# i2c1.net
KiCad netlist of a schematic drawn in Altium Designer
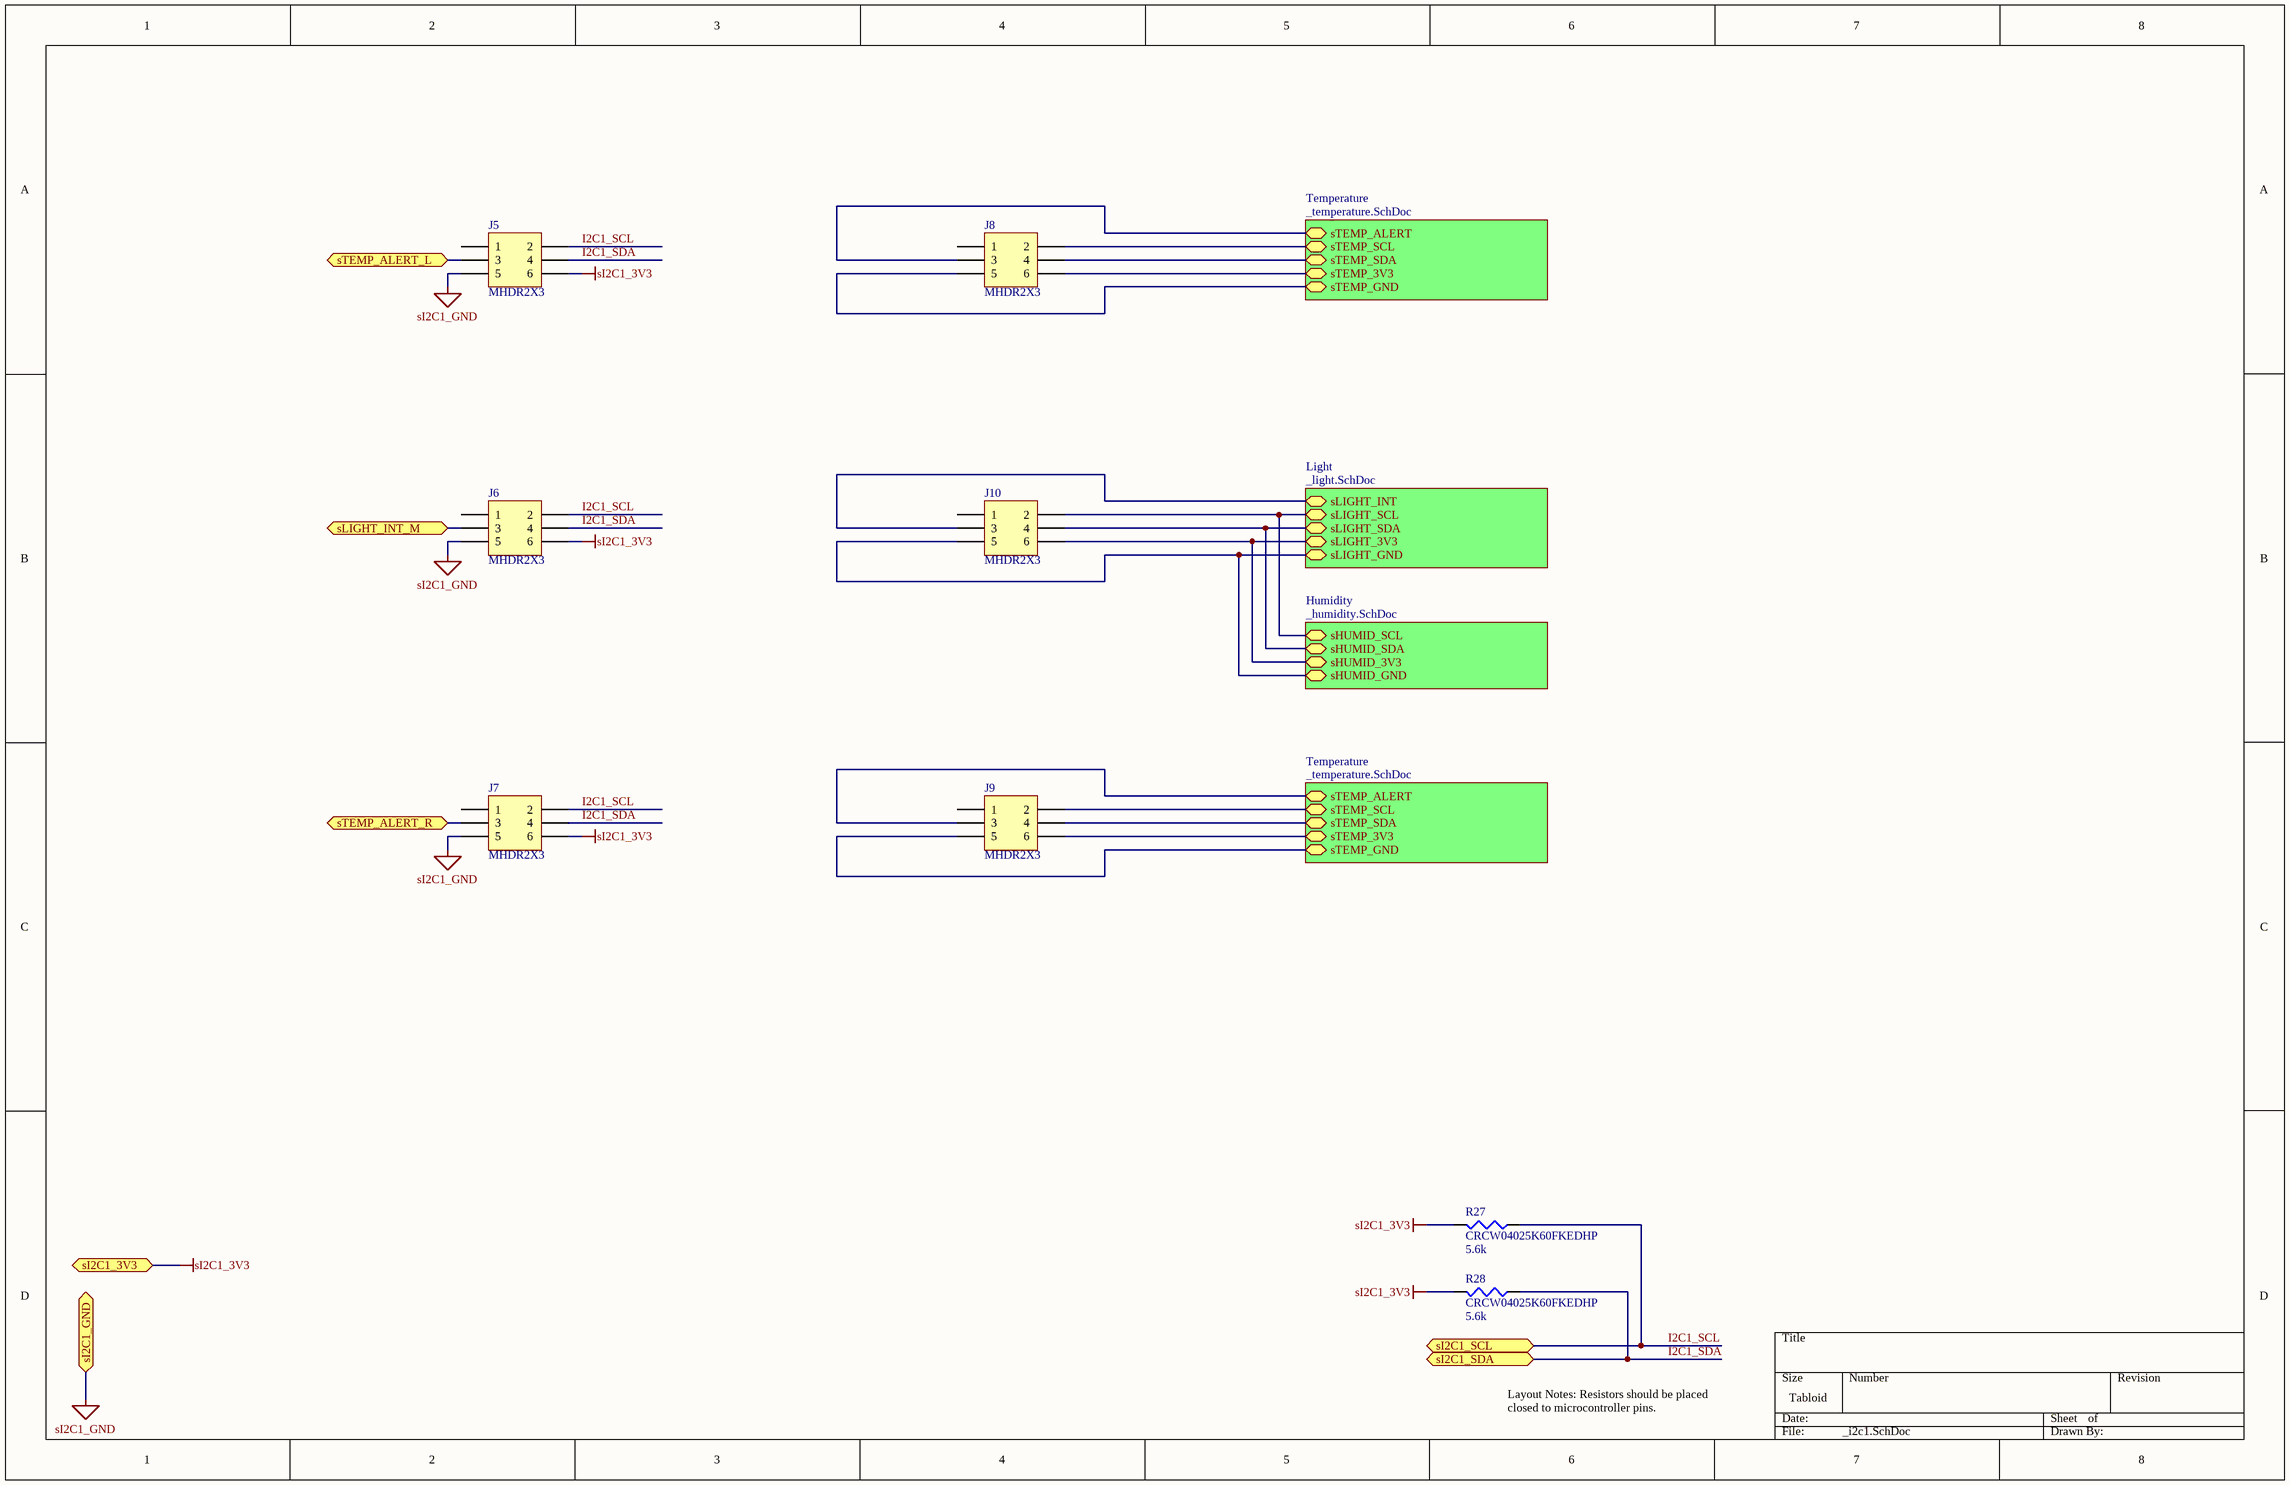
[diagram p0: _i2c1.SchDoc]

(export (version "E")
  (design (tool "Eeschema 10.0.6"))
  (components
    (comp (ref "J5")
      (value "MHDR2X3")
      (footprint "MHDR2X3")
      (description "Header, 3-Pin, Dual row")
      (fields (field (name "PUBLISHER") "Altium Limited"))
      (libsource (lib "Miscellaneous Connectors") (part "MHDR2X3"))
    )
    (comp (ref "J6")
      (value "MHDR2X3")
      (footprint "MHDR2X3")
      (description "Header, 3-Pin, Dual row")
      (fields (field (name "PUBLISHER") "Altium Limited"))
      (libsource (lib "Miscellaneous Connectors") (part "MHDR2X3"))
    )
    (comp (ref "J7")
      (value "MHDR2X3")
      (footprint "MHDR2X3")
      (description "Header, 3-Pin, Dual row")
      (fields (field (name "PUBLISHER") "Altium Limited"))
      (libsource (lib "Miscellaneous Connectors") (part "MHDR2X3"))
    )
    (comp (ref "J8")
      (value "MHDR2X3")
      (footprint "MHDR2X3")
      (description "Header, 3-Pin, Dual row")
      (fields (field (name "PUBLISHER") "Altium Limited"))
      (libsource (lib "Miscellaneous Connectors") (part "MHDR2X3"))
    )
    (comp (ref "J9")
      (value "MHDR2X3")
      (footprint "MHDR2X3")
      (description "Header, 3-Pin, Dual row")
      (fields (field (name "PUBLISHER") "Altium Limited"))
      (libsource (lib "Miscellaneous Connectors") (part "MHDR2X3"))
    )
    (comp (ref "J10")
      (value "MHDR2X3")
      (footprint "MHDR2X3")
      (description "Header, 3-Pin, Dual row")
      (fields (field (name "PUBLISHER") "Altium Limited"))
      (libsource (lib "Miscellaneous Connectors") (part "MHDR2X3"))
    )
    (comp (ref "R27")
      (value "CRCW04025K60FKEDHP")
      (footprint "0402")
      (description "0.125W, -55-155C, 1005, 50V, ±1%")
      (fields (field (name "ALTIUM_VALUE") "5.6k"))
      (libsource (lib "standard_resistors") (part "CRCW0402xxxxFKED"))
    )
    (comp (ref "R28")
      (value "CRCW04025K60FKEDHP")
      (footprint "0402")
      (description "0.125W, -55-155C, 1005, 50V, ±1%")
      (fields (field (name "ALTIUM_VALUE") "5.6k"))
      (libsource (lib "standard_resistors") (part "CRCW0402xxxxFKED"))
    )
  )
  (nets
    (net (code "1") (name "/I2C1_SCL") (class "Default")
      (node (ref "J5") (pin "2") (pinfunction "2_2") (pintype "passive"))
      (node (ref "J6") (pin "2") (pinfunction "2_2") (pintype "passive"))
      (node (ref "J7") (pin "2") (pinfunction "2_2") (pintype "passive"))
      (node (ref "R27") (pin "1") (pinfunction "1_1") (pintype "passive"))
    )
    (net (code "2") (name "/I2C1_SDA") (class "Default")
      (node (ref "J5") (pin "4") (pinfunction "4_4") (pintype "passive"))
      (node (ref "J6") (pin "4") (pinfunction "4_4") (pintype "passive"))
      (node (ref "J7") (pin "4") (pinfunction "4_4") (pintype "passive"))
      (node (ref "R28") (pin "1") (pinfunction "1_1") (pintype "passive"))
    )
    (net (code "3") (name "/sHUMID_3V3") (class "Default")
      (node (ref "J10") (pin "6") (pinfunction "6_6") (pintype "passive"))
    )
    (net (code "4") (name "/sHUMID_GND") (class "Default")
      (node (ref "J10") (pin "5") (pinfunction "5_5") (pintype "passive"))
    )
    (net (code "5") (name "/sHUMID_SCL") (class "Default")
      (node (ref "J10") (pin "2") (pinfunction "2_2") (pintype "passive"))
    )
    (net (code "6") (name "/sHUMID_SDA") (class "Default")
      (node (ref "J10") (pin "4") (pinfunction "4_4") (pintype "passive"))
    )
    (net (code "7") (name "/sLIGHT_INT") (class "Default")
      (node (ref "J10") (pin "3") (pinfunction "3_3") (pintype "passive"))
    )
    (net (code "8") (name "/sLIGHT_INT_M") (class "Default")
      (node (ref "J6") (pin "3") (pinfunction "3_3") (pintype "passive"))
    )
    (net (code "9") (name "/sTEMP_3V3") (class "Default")
      (node (ref "J8") (pin "6") (pinfunction "6_6") (pintype "passive"))
    )
    (net (code "10") (name "/sTEMP_3V3_1") (class "Default")
      (node (ref "J9") (pin "6") (pinfunction "6_6") (pintype "passive"))
    )
    (net (code "11") (name "/sTEMP_ALERT") (class "Default")
      (node (ref "J8") (pin "3") (pinfunction "3_3") (pintype "passive"))
    )
    (net (code "12") (name "/sTEMP_ALERT_1") (class "Default")
      (node (ref "J9") (pin "3") (pinfunction "3_3") (pintype "passive"))
    )
    (net (code "13") (name "/sTEMP_ALERT_L") (class "Default")
      (node (ref "J5") (pin "3") (pinfunction "3_3") (pintype "passive"))
    )
    (net (code "14") (name "/sTEMP_ALERT_R") (class "Default")
      (node (ref "J7") (pin "3") (pinfunction "3_3") (pintype "passive"))
    )
    (net (code "15") (name "/sTEMP_GND") (class "Default")
      (node (ref "J8") (pin "5") (pinfunction "5_5") (pintype "passive"))
    )
    (net (code "16") (name "/sTEMP_GND_1") (class "Default")
      (node (ref "J9") (pin "5") (pinfunction "5_5") (pintype "passive"))
    )
    (net (code "17") (name "/sTEMP_SCL") (class "Default")
      (node (ref "J8") (pin "2") (pinfunction "2_2") (pintype "passive"))
    )
    (net (code "18") (name "/sTEMP_SCL_1") (class "Default")
      (node (ref "J9") (pin "2") (pinfunction "2_2") (pintype "passive"))
    )
    (net (code "19") (name "/sTEMP_SDA") (class "Default")
      (node (ref "J8") (pin "4") (pinfunction "4_4") (pintype "passive"))
    )
    (net (code "20") (name "/sTEMP_SDA_1") (class "Default")
      (node (ref "J9") (pin "4") (pinfunction "4_4") (pintype "passive"))
    )
    (net (code "21") (name "sI2C1_3V3") (class "Default")
      (node (ref "J5") (pin "6") (pinfunction "6_6") (pintype "passive"))
      (node (ref "J6") (pin "6") (pinfunction "6_6") (pintype "passive"))
      (node (ref "J7") (pin "6") (pinfunction "6_6") (pintype "passive"))
      (node (ref "R27") (pin "2") (pinfunction "2_2") (pintype "passive"))
      (node (ref "R28") (pin "2") (pinfunction "2_2") (pintype "passive"))
    )
    (net (code "22") (name "sI2C1_GND") (class "Default")
      (node (ref "J5") (pin "5") (pinfunction "5_5") (pintype "passive"))
      (node (ref "J6") (pin "5") (pinfunction "5_5") (pintype "passive"))
      (node (ref "J7") (pin "5") (pinfunction "5_5") (pintype "passive"))
    )
    (net (code "23") (name "unconnected-(J5-Pad1)") (class "Default")
      (node (ref "J5") (pin "1") (pinfunction "1_1") (pintype "passive"))
    )
    (net (code "24") (name "unconnected-(J6-Pad1)") (class "Default")
      (node (ref "J6") (pin "1") (pinfunction "1_1") (pintype "passive"))
    )
    (net (code "25") (name "unconnected-(J7-Pad1)") (class "Default")
      (node (ref "J7") (pin "1") (pinfunction "1_1") (pintype "passive"))
    )
    (net (code "26") (name "unconnected-(J8-Pad1)") (class "Default")
      (node (ref "J8") (pin "1") (pinfunction "1_1") (pintype "passive"))
    )
    (net (code "27") (name "unconnected-(J9-Pad1)") (class "Default")
      (node (ref "J9") (pin "1") (pinfunction "1_1") (pintype "passive"))
    )
    (net (code "28") (name "unconnected-(J10-Pad1)") (class "Default")
      (node (ref "J10") (pin "1") (pinfunction "1_1") (pintype "passive"))
    )
  )
)
